# FPGA_B14_B16.net
KiCad netlist of a schematic drawn in Altium Designer
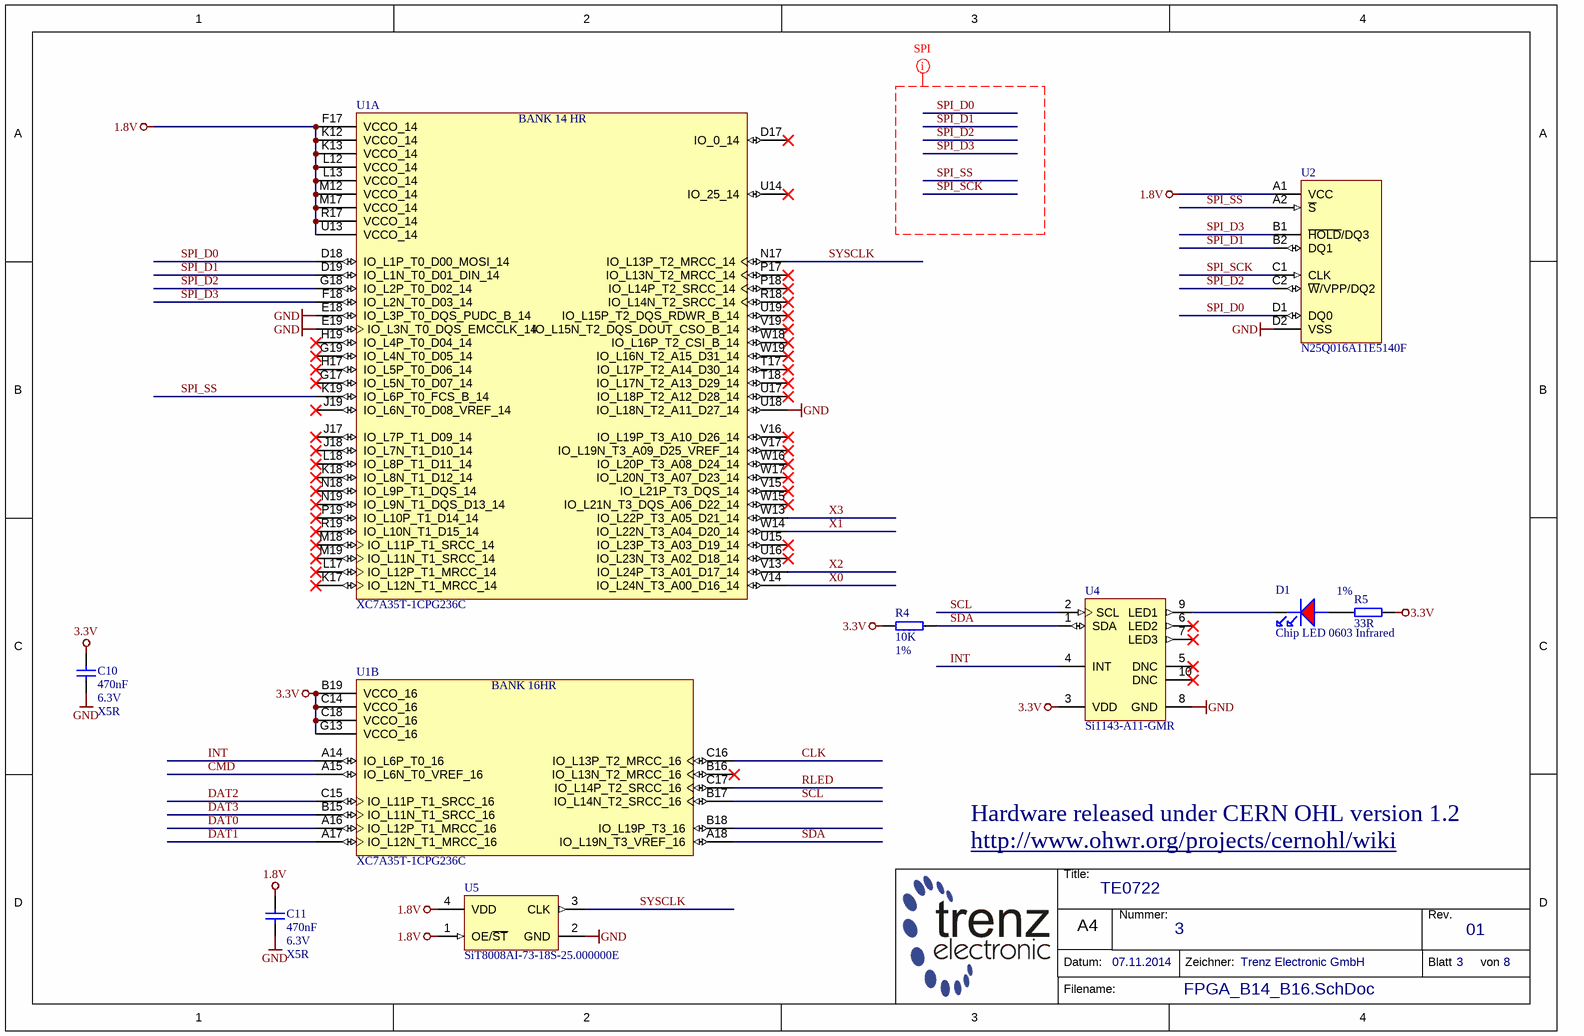
[diagram p0: FPGA_B14_B16.SchDoc]

(export (version "E")
  (design (tool "Eeschema 10.0.6"))
  (components
    (comp (ref "C10")
      (value "470nF")
      (footprint "CAPC0603X33N")
      (description "KON 470nF X5R 6.3V SMD 20%")
      (fields
        (field (name "VOLTAGE") "6.3V")
        (field (name "TECHNOLOGY") "X5R")
        (field (name "TOLERANCE") "20%")
      )
      (libsource (lib "TE") (part "CAP-NP"))
    )
    (comp (ref "C11")
      (value "470nF")
      (footprint "CAPC0603X33N")
      (description "KON 470nF X5R 6.3V SMD 20%")
      (fields
        (field (name "VOLTAGE") "6.3V")
        (field (name "TECHNOLOGY") "X5R")
        (field (name "TOLERANCE") "20%")
      )
      (libsource (lib "TE") (part "CAP-NP"))
    )
    (comp (ref "D1")
      (value "Chip LED 0603 Infrared")
      (footprint "chipLED_0603_Red")
      (fields (field (name "VOLTAGE") "1.2"))
      (libsource (lib "TE") (part "LED_ROT"))
    )
    (comp (ref "R4")
      (value "10K")
      (footprint "RESC0603X26N")
      (description "WID SMD 10K 1% 0,05W")
      (fields (field (name "TOLERANCE") "1%"))
      (libsource (lib "TE") (part "RES"))
    )
    (comp (ref "R5")
      (value "33R")
      (footprint "RESC1005X40N")
      (description "WID SMD 33R 1% 0,063W")
      (fields (field (name "TOLERANCE") "1%"))
      (libsource (lib "TE") (part "RES"))
    )
    (comp (ref "U1")
      (value "XC7A35T-1CPG236C")
      (footprint "XC7AxxT-CPG236")
      (libsource (lib "TE") (part "XC7A35T-CPG236"))
    )
    (comp (ref "U2")
      (value "N25Q016A11E5140F")
      (footprint "BGA8C50P4X2_271X196X41B30N")
      (libsource (lib "TE") (part "N25Q016A11E"))
    )
    (comp (ref "U4")
      (value "Si1143-A11-GMR")
      (footprint "QFN50P200X200X75-10N")
      (libsource (lib "TE") (part "Si1143"))
    )
    (comp (ref "U5")
      (value "SiT8008AI-73-18S-25.000000E")
      (footprint "2016")
      (description "SiT8008AI-73-18S-25.000000E MEMS Oszillator 25MHz")
      (fields (field (name "VOLTAGE") "1.8V"))
      (libsource (lib "TE") (part "SiT8103"))
    )
  )
  (nets
    (net (code "1") (name "/CLK") (class "Default")
      (node (ref "U1") (pin "C16") (pinfunction "IO_L13P_T2_MRCC_16_C16") (pintype "bidirectional"))
    )
    (net (code "2") (name "/CMD") (class "Default")
      (node (ref "U1") (pin "A15") (pinfunction "IO_L6N_T0_VREF_16_A15") (pintype "bidirectional"))
    )
    (net (code "3") (name "/DAT0") (class "Default")
      (node (ref "U1") (pin "A16") (pinfunction "IO_L12P_T1_MRCC_16_A16") (pintype "bidirectional"))
    )
    (net (code "4") (name "/DAT1") (class "Default")
      (node (ref "U1") (pin "A17") (pinfunction "IO_L12N_T1_MRCC_16_A17") (pintype "bidirectional"))
    )
    (net (code "5") (name "/DAT2") (class "Default")
      (node (ref "U1") (pin "C15") (pinfunction "IO_L11P_T1_SRCC_16_C15") (pintype "bidirectional"))
    )
    (net (code "6") (name "/DAT3") (class "Default")
      (node (ref "U1") (pin "B15") (pinfunction "IO_L11N_T1_SRCC_16_B15") (pintype "bidirectional"))
    )
    (net (code "7") (name "/INT") (class "Default")
      (node (ref "U1") (pin "A14") (pinfunction "IO_L6P_T0_16_A14") (pintype "bidirectional"))
      (node (ref "U4") (pin "4") (pinfunction "INT_4") (pintype "open_collector"))
    )
    (net (code "8") (name "/RLED") (class "Default")
      (node (ref "U1") (pin "C17") (pinfunction "IO_L14P_T2_SRCC_16_C17") (pintype "bidirectional"))
    )
    (net (code "9") (name "/SCL") (class "Default")
      (node (ref "U1") (pin "B17") (pinfunction "IO_L14N_T2_SRCC_16_B17") (pintype "bidirectional"))
      (node (ref "U4") (pin "2") (pinfunction "SCL_2") (pintype "input"))
    )
    (net (code "10") (name "/SDA") (class "Default")
      (node (ref "R4") (pin "2") (pinfunction "2_2") (pintype "passive"))
      (node (ref "U1") (pin "A18") (pinfunction "IO_L19N_T3_VREF_16_A18") (pintype "bidirectional"))
      (node (ref "U4") (pin "1") (pinfunction "SDA_1") (pintype "bidirectional"))
    )
    (net (code "11") (name "/SPI_D0") (class "Default")
      (node (ref "U1") (pin "D18") (pinfunction "IO_L1P_T0_D00_MOSI_14_D18") (pintype "bidirectional"))
      (node (ref "U2") (pin "D1") (pinfunction "DQ0_D1") (pintype "bidirectional"))
    )
    (net (code "12") (name "/SPI_D1") (class "Default")
      (node (ref "U1") (pin "D19") (pinfunction "IO_L1N_T0_D01_DIN_14_D19") (pintype "bidirectional"))
      (node (ref "U2") (pin "B2") (pinfunction "DQ1_B2") (pintype "bidirectional"))
    )
    (net (code "13") (name "/SPI_D2") (class "Default")
      (node (ref "U1") (pin "G18") (pinfunction "IO_L2P_T0_D02_14_G18") (pintype "bidirectional"))
      (node (ref "U2") (pin "C2") (pinfunction "~{W}/VPP/DQ2_C2") (pintype "bidirectional"))
    )
    (net (code "14") (name "/SPI_D3") (class "Default")
      (node (ref "U1") (pin "F18") (pinfunction "IO_L2N_T0_D03_14_F18") (pintype "bidirectional"))
      (node (ref "U2") (pin "B1") (pinfunction "~{HOLD}/DQ3_B1") (pintype "passive"))
    )
    (net (code "15") (name "/SPI_SCK") (class "Default")
      (node (ref "U2") (pin "C1") (pinfunction "CLK_C1") (pintype "input"))
    )
    (net (code "16") (name "/SPI_SS") (class "Default")
      (node (ref "U1") (pin "K19") (pinfunction "IO_L6P_T0_FCS_B_14_K19") (pintype "bidirectional"))
      (node (ref "U2") (pin "A2") (pinfunction "~{S}_A2") (pintype "input"))
    )
    (net (code "17") (name "/SYSCLK") (class "Default")
      (node (ref "U1") (pin "N17") (pinfunction "IO_L13P_T2_MRCC_14_N17") (pintype "bidirectional"))
      (node (ref "U5") (pin "3") (pinfunction "CLK_3") (pintype "output"))
    )
    (net (code "18") (name "/X0") (class "Default")
      (node (ref "U1") (pin "V14") (pinfunction "IO_L24N_T3_A00_D16_14_V14") (pintype "bidirectional"))
    )
    (net (code "19") (name "/X1") (class "Default")
      (node (ref "U1") (pin "W14") (pinfunction "IO_L22N_T3_A04_D20_14_W14") (pintype "bidirectional"))
    )
    (net (code "20") (name "/X2") (class "Default")
      (node (ref "U1") (pin "V13") (pinfunction "IO_L24P_T3_A01_D17_14_V13") (pintype "bidirectional"))
    )
    (net (code "21") (name "/X3") (class "Default")
      (node (ref "U1") (pin "W13") (pinfunction "IO_L22P_T3_A05_D21_14_W13") (pintype "bidirectional"))
    )
    (net (code "22") (name "1.8V") (class "Default")
      (node (ref "C11") (pin "1") (pinfunction "1_1") (pintype "passive"))
      (node (ref "U1") (pin "F17") (pinfunction "VCCO_14_F17") (pintype "power_in"))
      (node (ref "U1") (pin "K12") (pinfunction "VCCO_14_K12") (pintype "power_in"))
      (node (ref "U1") (pin "K13") (pinfunction "VCCO_14_K13") (pintype "power_in"))
      (node (ref "U1") (pin "L12") (pinfunction "VCCO_14_L12") (pintype "power_in"))
      (node (ref "U1") (pin "L13") (pinfunction "VCCO_14_L13") (pintype "power_in"))
      (node (ref "U1") (pin "M12") (pinfunction "VCCO_14_M12") (pintype "power_in"))
      (node (ref "U1") (pin "M17") (pinfunction "VCCO_14_M17") (pintype "power_in"))
      (node (ref "U1") (pin "R17") (pinfunction "VCCO_14_R17") (pintype "power_in"))
      (node (ref "U1") (pin "U13") (pinfunction "VCCO_14_U13") (pintype "power_in"))
      (node (ref "U2") (pin "A1") (pinfunction "VCC_A1") (pintype "power_in"))
      (node (ref "U5") (pin "1") (pinfunction "OE/~{ST}_1") (pintype "input"))
      (node (ref "U5") (pin "4") (pinfunction "VDD_4") (pintype "power_in"))
    )
    (net (code "23") (name "3.3V") (class "Default")
      (node (ref "C10") (pin "1") (pinfunction "1_1") (pintype "passive"))
      (node (ref "R4") (pin "1") (pinfunction "1_1") (pintype "passive"))
      (node (ref "R5") (pin "2") (pinfunction "2_2") (pintype "passive"))
      (node (ref "U1") (pin "B19") (pinfunction "VCCO_16_B19") (pintype "power_in"))
      (node (ref "U1") (pin "C14") (pinfunction "VCCO_16_C14") (pintype "power_in"))
      (node (ref "U1") (pin "C18") (pinfunction "VCCO_16_C18") (pintype "power_in"))
      (node (ref "U1") (pin "G13") (pinfunction "VCCO_16_G13") (pintype "power_in"))
      (node (ref "U4") (pin "3") (pinfunction "VDD_3") (pintype "power_in"))
    )
    (net (code "24") (name "GND") (class "Default")
      (node (ref "C10") (pin "2") (pinfunction "2_2") (pintype "passive"))
      (node (ref "C11") (pin "2") (pinfunction "2_2") (pintype "passive"))
      (node (ref "U1") (pin "E18") (pinfunction "IO_L3P_T0_DQS_PUDC_B_14_E18") (pintype "bidirectional"))
      (node (ref "U1") (pin "E19") (pinfunction "IO_L3N_T0_DQS_EMCCLK_14_E19") (pintype "bidirectional"))
      (node (ref "U1") (pin "U18") (pinfunction "IO_L18N_T2_A11_D27_14_U18") (pintype "bidirectional"))
      (node (ref "U2") (pin "D2") (pinfunction "VSS_D2") (pintype "power_in"))
      (node (ref "U4") (pin "8") (pinfunction "GND_8") (pintype "power_in"))
      (node (ref "U5") (pin "2") (pinfunction "GND_2") (pintype "power_in"))
    )
    (net (code "25") (name "Net-(D1-PadA)") (class "Default")
      (node (ref "D1") (pin "A") (pinfunction "A_A") (pintype "passive"))
      (node (ref "R5") (pin "1") (pinfunction "1_1") (pintype "passive"))
    )
    (net (code "26") (name "Net-(U4-LED1)") (class "Default")
      (node (ref "D1") (pin "K") (pinfunction "K_K") (pintype "passive"))
      (node (ref "U4") (pin "9") (pinfunction "LED1_9") (pintype "output"))
    )
    (net (code "27") (name "unconnected-(U1A-IO_0_14-PadD17)") (class "Default")
      (node (ref "U1") (pin "D17") (pinfunction "IO_0_14_D17") (pintype "bidirectional+no_connect"))
    )
    (net (code "28") (name "unconnected-(U1A-IO_25_14-PadU14)") (class "Default")
      (node (ref "U1") (pin "U14") (pinfunction "IO_25_14_U14") (pintype "bidirectional+no_connect"))
    )
    (net (code "29") (name "unconnected-(U1A-IO_L4N_T0_D05_14-PadG19)") (class "Default")
      (node (ref "U1") (pin "G19") (pinfunction "IO_L4N_T0_D05_14_G19") (pintype "bidirectional+no_connect"))
    )
    (net (code "30") (name "unconnected-(U1A-IO_L4P_T0_D04_14-PadH19)") (class "Default")
      (node (ref "U1") (pin "H19") (pinfunction "IO_L4P_T0_D04_14_H19") (pintype "bidirectional+no_connect"))
    )
    (net (code "31") (name "unconnected-(U1A-IO_L5N_T0_D07_14-PadG17)") (class "Default")
      (node (ref "U1") (pin "G17") (pinfunction "IO_L5N_T0_D07_14_G17") (pintype "bidirectional+no_connect"))
    )
    (net (code "32") (name "unconnected-(U1A-IO_L5P_T0_D06_14-PadH17)") (class "Default")
      (node (ref "U1") (pin "H17") (pinfunction "IO_L5P_T0_D06_14_H17") (pintype "bidirectional+no_connect"))
    )
    (net (code "33") (name "unconnected-(U1A-IO_L6N_T0_D08_VREF_14-PadJ19)") (class "Default")
      (node (ref "U1") (pin "J19") (pinfunction "IO_L6N_T0_D08_VREF_14_J19") (pintype "bidirectional+no_connect"))
    )
    (net (code "34") (name "unconnected-(U1A-IO_L7N_T1_D10_14-PadJ18)") (class "Default")
      (node (ref "U1") (pin "J18") (pinfunction "IO_L7N_T1_D10_14_J18") (pintype "bidirectional+no_connect"))
    )
    (net (code "35") (name "unconnected-(U1A-IO_L7P_T1_D09_14-PadJ17)") (class "Default")
      (node (ref "U1") (pin "J17") (pinfunction "IO_L7P_T1_D09_14_J17") (pintype "bidirectional+no_connect"))
    )
    (net (code "36") (name "unconnected-(U1A-IO_L8N_T1_D12_14-PadK18)") (class "Default")
      (node (ref "U1") (pin "K18") (pinfunction "IO_L8N_T1_D12_14_K18") (pintype "bidirectional+no_connect"))
    )
    (net (code "37") (name "unconnected-(U1A-IO_L8P_T1_D11_14-PadL18)") (class "Default")
      (node (ref "U1") (pin "L18") (pinfunction "IO_L8P_T1_D11_14_L18") (pintype "bidirectional+no_connect"))
    )
    (net (code "38") (name "unconnected-(U1A-IO_L9N_T1_DQS_D13_14-PadN19)") (class "Default")
      (node (ref "U1") (pin "N19") (pinfunction "IO_L9N_T1_DQS_D13_14_N19") (pintype "bidirectional+no_connect"))
    )
    (net (code "39") (name "unconnected-(U1A-IO_L9P_T1_DQS_14-PadN18)") (class "Default")
      (node (ref "U1") (pin "N18") (pinfunction "IO_L9P_T1_DQS_14_N18") (pintype "bidirectional+no_connect"))
    )
    (net (code "40") (name "unconnected-(U1A-IO_L10N_T1_D15_14-PadR19)") (class "Default")
      (node (ref "U1") (pin "R19") (pinfunction "IO_L10N_T1_D15_14_R19") (pintype "bidirectional+no_connect"))
    )
    (net (code "41") (name "unconnected-(U1A-IO_L10P_T1_D14_14-PadP19)") (class "Default")
      (node (ref "U1") (pin "P19") (pinfunction "IO_L10P_T1_D14_14_P19") (pintype "bidirectional+no_connect"))
    )
    (net (code "42") (name "unconnected-(U1A-IO_L11N_T1_SRCC_14-PadM19)") (class "Default")
      (node (ref "U1") (pin "M19") (pinfunction "IO_L11N_T1_SRCC_14_M19") (pintype "bidirectional+no_connect"))
    )
    (net (code "43") (name "unconnected-(U1A-IO_L11P_T1_SRCC_14-PadM18)") (class "Default")
      (node (ref "U1") (pin "M18") (pinfunction "IO_L11P_T1_SRCC_14_M18") (pintype "bidirectional+no_connect"))
    )
    (net (code "44") (name "unconnected-(U1A-IO_L12N_T1_MRCC_14-PadK17)") (class "Default")
      (node (ref "U1") (pin "K17") (pinfunction "IO_L12N_T1_MRCC_14_K17") (pintype "bidirectional+no_connect"))
    )
    (net (code "45") (name "unconnected-(U1A-IO_L12P_T1_MRCC_14-PadL17)") (class "Default")
      (node (ref "U1") (pin "L17") (pinfunction "IO_L12P_T1_MRCC_14_L17") (pintype "bidirectional+no_connect"))
    )
    (net (code "46") (name "unconnected-(U1A-IO_L13N_T2_MRCC_14-PadP17)") (class "Default")
      (node (ref "U1") (pin "P17") (pinfunction "IO_L13N_T2_MRCC_14_P17") (pintype "bidirectional+no_connect"))
    )
    (net (code "47") (name "unconnected-(U1A-IO_L14N_T2_SRCC_14-PadR18)") (class "Default")
      (node (ref "U1") (pin "R18") (pinfunction "IO_L14N_T2_SRCC_14_R18") (pintype "bidirectional+no_connect"))
    )
    (net (code "48") (name "unconnected-(U1A-IO_L14P_T2_SRCC_14-PadP18)") (class "Default")
      (node (ref "U1") (pin "P18") (pinfunction "IO_L14P_T2_SRCC_14_P18") (pintype "bidirectional+no_connect"))
    )
    (net (code "49") (name "unconnected-(U1A-IO_L15N_T2_DQS_DOUT_CSO_B_14-PadV19)") (class "Default")
      (node (ref "U1") (pin "V19") (pinfunction "IO_L15N_T2_DQS_DOUT_CSO_B_14_V19") (pintype "bidirectional+no_connect"))
    )
    (net (code "50") (name "unconnected-(U1A-IO_L15P_T2_DQS_RDWR_B_14-PadU19)") (class "Default")
      (node (ref "U1") (pin "U19") (pinfunction "IO_L15P_T2_DQS_RDWR_B_14_U19") (pintype "bidirectional+no_connect"))
    )
    (net (code "51") (name "unconnected-(U1A-IO_L16N_T2_A15_D31_14-PadW19)") (class "Default")
      (node (ref "U1") (pin "W19") (pinfunction "IO_L16N_T2_A15_D31_14_W19") (pintype "bidirectional+no_connect"))
    )
    (net (code "52") (name "unconnected-(U1A-IO_L16P_T2_CSI_B_14-PadW18)") (class "Default")
      (node (ref "U1") (pin "W18") (pinfunction "IO_L16P_T2_CSI_B_14_W18") (pintype "bidirectional+no_connect"))
    )
    (net (code "53") (name "unconnected-(U1A-IO_L17N_T2_A13_D29_14-PadT18)") (class "Default")
      (node (ref "U1") (pin "T18") (pinfunction "IO_L17N_T2_A13_D29_14_T18") (pintype "bidirectional+no_connect"))
    )
    (net (code "54") (name "unconnected-(U1A-IO_L17P_T2_A14_D30_14-PadT17)") (class "Default")
      (node (ref "U1") (pin "T17") (pinfunction "IO_L17P_T2_A14_D30_14_T17") (pintype "bidirectional+no_connect"))
    )
    (net (code "55") (name "unconnected-(U1A-IO_L18P_T2_A12_D28_14-PadU17)") (class "Default")
      (node (ref "U1") (pin "U17") (pinfunction "IO_L18P_T2_A12_D28_14_U17") (pintype "bidirectional+no_connect"))
    )
    (net (code "56") (name "unconnected-(U1A-IO_L19N_T3_A09_D25_VREF_14-PadV17)") (class "Default")
      (node (ref "U1") (pin "V17") (pinfunction "IO_L19N_T3_A09_D25_VREF_14_V17") (pintype "bidirectional+no_connect"))
    )
    (net (code "57") (name "unconnected-(U1A-IO_L19P_T3_A10_D26_14-PadV16)") (class "Default")
      (node (ref "U1") (pin "V16") (pinfunction "IO_L19P_T3_A10_D26_14_V16") (pintype "bidirectional+no_connect"))
    )
    (net (code "58") (name "unconnected-(U1A-IO_L20N_T3_A07_D23_14-PadW17)") (class "Default")
      (node (ref "U1") (pin "W17") (pinfunction "IO_L20N_T3_A07_D23_14_W17") (pintype "bidirectional+no_connect"))
    )
    (net (code "59") (name "unconnected-(U1A-IO_L20P_T3_A08_D24_14-PadW16)") (class "Default")
      (node (ref "U1") (pin "W16") (pinfunction "IO_L20P_T3_A08_D24_14_W16") (pintype "bidirectional+no_connect"))
    )
    (net (code "60") (name "unconnected-(U1A-IO_L21N_T3_DQS_A06_D22_14-PadW15)") (class "Default")
      (node (ref "U1") (pin "W15") (pinfunction "IO_L21N_T3_DQS_A06_D22_14_W15") (pintype "bidirectional+no_connect"))
    )
    (net (code "61") (name "unconnected-(U1A-IO_L21P_T3_DQS_14-PadV15)") (class "Default")
      (node (ref "U1") (pin "V15") (pinfunction "IO_L21P_T3_DQS_14_V15") (pintype "bidirectional+no_connect"))
    )
    (net (code "62") (name "unconnected-(U1A-IO_L23N_T3_A02_D18_14-PadU16)") (class "Default")
      (node (ref "U1") (pin "U16") (pinfunction "IO_L23N_T3_A02_D18_14_U16") (pintype "bidirectional+no_connect"))
    )
    (net (code "63") (name "unconnected-(U1A-IO_L23P_T3_A03_D19_14-PadU15)") (class "Default")
      (node (ref "U1") (pin "U15") (pinfunction "IO_L23P_T3_A03_D19_14_U15") (pintype "bidirectional+no_connect"))
    )
    (net (code "64") (name "unconnected-(U1B-IO_L13N_T2_MRCC_16-PadB16)") (class "Default")
      (node (ref "U1") (pin "B16") (pinfunction "IO_L13N_T2_MRCC_16_B16") (pintype "bidirectional+no_connect"))
    )
    (net (code "65") (name "unconnected-(U1B-IO_L19P_T3_16-PadB18)") (class "Default")
      (node (ref "U1") (pin "B18") (pinfunction "IO_L19P_T3_16_B18") (pintype "bidirectional"))
    )
    (net (code "66") (name "unconnected-(U4-DNC-Pad5)") (class "Default")
      (node (ref "U4") (pin "5") (pinfunction "DNC_5") (pintype "passive+no_connect"))
    )
    (net (code "67") (name "unconnected-(U4-DNC-Pad10)") (class "Default")
      (node (ref "U4") (pin "10") (pinfunction "DNC_10") (pintype "passive+no_connect"))
    )
    (net (code "68") (name "unconnected-(U4-LED2-Pad6)") (class "Default")
      (node (ref "U4") (pin "6") (pinfunction "LED2_6") (pintype "output+no_connect"))
    )
    (net (code "69") (name "unconnected-(U4-LED3-Pad7)") (class "Default")
      (node (ref "U4") (pin "7") (pinfunction "LED3_7") (pintype "output+no_connect"))
    )
  )
)
